# Connectors.net
KiCad netlist of a schematic drawn in Altium Designer
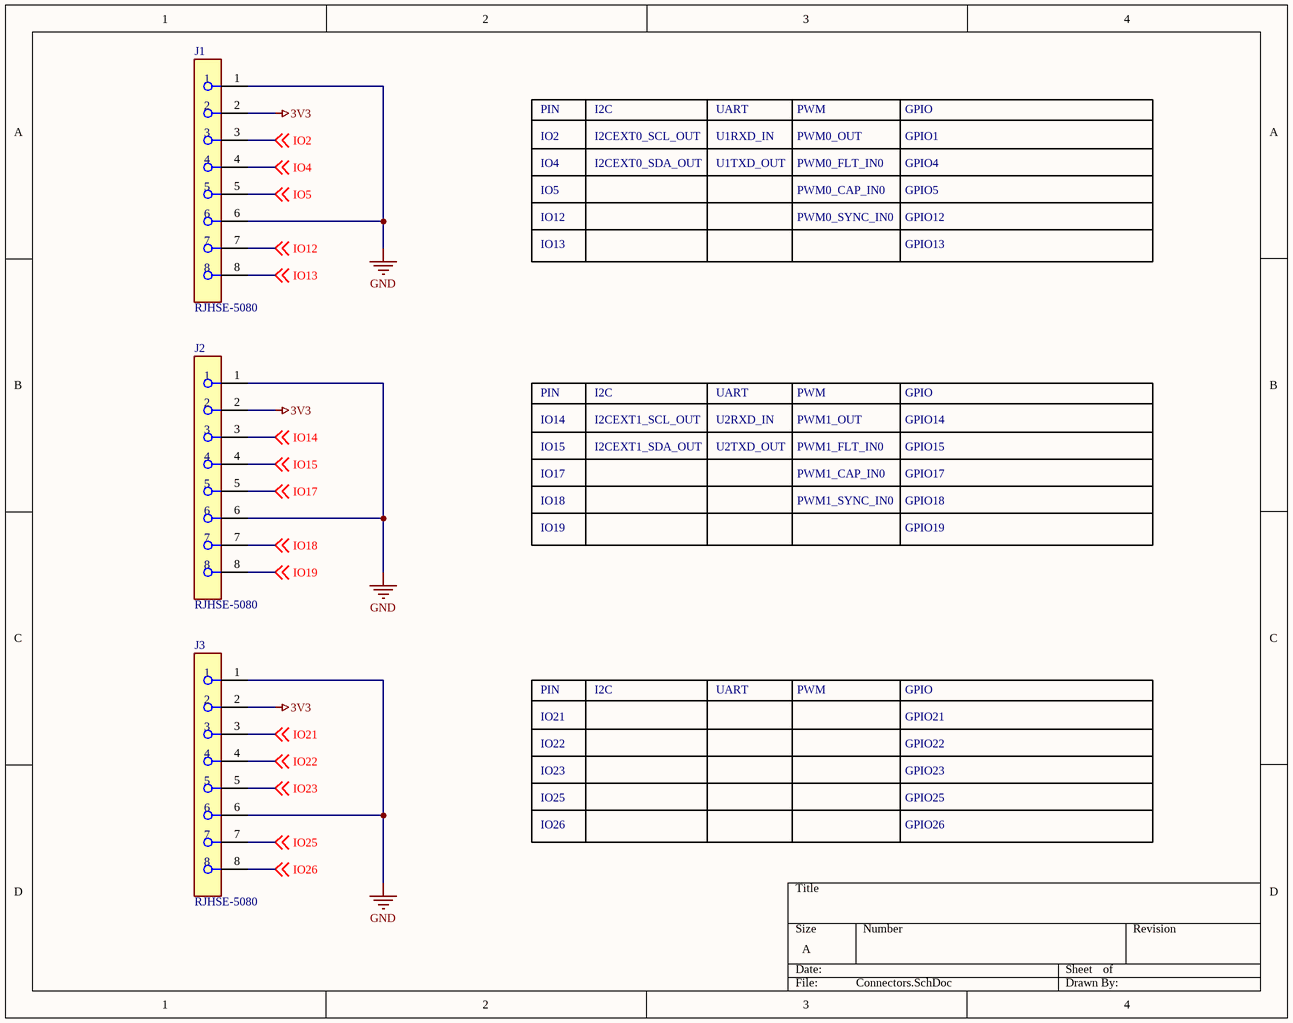
[diagram p0: Connectors.SchDoc]

(export (version "E")
  (design (tool "Eeschema 10.0.6"))
  (components
    (comp (ref "J1")
      (value "RJHSE-5080")
      (footprint "FP-RJHSE-5080-MFG")
      (description "CONN MOD JACK 8P8C R/A UNSHLD")
      (fields
        (field (name "OCTOPART") "https://octopart.com/rjhse-5080-amphenol-45060")
        (field (name "MANUFACTURER") "Amphenol")
      )
      (libsource (lib "Altium Content Vault") (part "b0a0b555dd3abf3683e7c330df25cc4"))
    )
    (comp (ref "J2")
      (value "RJHSE-5080")
      (footprint "FP-RJHSE-5080-MFG")
      (description "CONN MOD JACK 8P8C R/A UNSHLD")
      (fields
        (field (name "OCTOPART") "https://octopart.com/rjhse-5080-amphenol-45060")
        (field (name "MANUFACTURER") "Amphenol")
      )
      (libsource (lib "Altium Content Vault") (part "b0a0b555dd3abf3683e7c330df25cc4"))
    )
    (comp (ref "J3")
      (value "RJHSE-5080")
      (footprint "FP-RJHSE-5080-MFG")
      (description "CONN MOD JACK 8P8C R/A UNSHLD")
      (fields
        (field (name "OCTOPART") "https://octopart.com/rjhse-5080-amphenol-45060")
        (field (name "MANUFACTURER") "Amphenol")
      )
      (libsource (lib "Altium Content Vault") (part "b0a0b555dd3abf3683e7c330df25cc4"))
    )
  )
  (nets
    (net (code "1") (name "3V3") (class "Default")
      (node (ref "J1") (pin "2") (pinfunction "2_2") (pintype "passive"))
      (node (ref "J2") (pin "2") (pinfunction "2_2") (pintype "passive"))
      (node (ref "J3") (pin "2") (pinfunction "2_2") (pintype "passive"))
    )
    (net (code "2") (name "GND") (class "Default")
      (node (ref "J1") (pin "1") (pinfunction "1_1") (pintype "passive"))
      (node (ref "J1") (pin "6") (pinfunction "6_6") (pintype "passive"))
      (node (ref "J2") (pin "1") (pinfunction "1_1") (pintype "passive"))
      (node (ref "J2") (pin "6") (pinfunction "6_6") (pintype "passive"))
      (node (ref "J3") (pin "1") (pinfunction "1_1") (pintype "passive"))
      (node (ref "J3") (pin "6") (pinfunction "6_6") (pintype "passive"))
    )
    (net (code "3") (name "IO2") (class "Default")
      (node (ref "J1") (pin "3") (pinfunction "3_3") (pintype "passive"))
    )
    (net (code "4") (name "IO4") (class "Default")
      (node (ref "J1") (pin "4") (pinfunction "4_4") (pintype "passive"))
    )
    (net (code "5") (name "IO5") (class "Default")
      (node (ref "J1") (pin "5") (pinfunction "5_5") (pintype "passive"))
    )
    (net (code "6") (name "IO12") (class "Default")
      (node (ref "J1") (pin "7") (pinfunction "7_7") (pintype "passive"))
    )
    (net (code "7") (name "IO13") (class "Default")
      (node (ref "J1") (pin "8") (pinfunction "8_8") (pintype "passive"))
    )
    (net (code "8") (name "IO14") (class "Default")
      (node (ref "J2") (pin "3") (pinfunction "3_3") (pintype "passive"))
    )
    (net (code "9") (name "IO15") (class "Default")
      (node (ref "J2") (pin "4") (pinfunction "4_4") (pintype "passive"))
    )
    (net (code "10") (name "IO17") (class "Default")
      (node (ref "J2") (pin "5") (pinfunction "5_5") (pintype "passive"))
    )
    (net (code "11") (name "IO18") (class "Default")
      (node (ref "J2") (pin "7") (pinfunction "7_7") (pintype "passive"))
    )
    (net (code "12") (name "IO19") (class "Default")
      (node (ref "J2") (pin "8") (pinfunction "8_8") (pintype "passive"))
    )
    (net (code "13") (name "IO21") (class "Default")
      (node (ref "J3") (pin "3") (pinfunction "3_3") (pintype "passive"))
    )
    (net (code "14") (name "IO22") (class "Default")
      (node (ref "J3") (pin "4") (pinfunction "4_4") (pintype "passive"))
    )
    (net (code "15") (name "IO23") (class "Default")
      (node (ref "J3") (pin "5") (pinfunction "5_5") (pintype "passive"))
    )
    (net (code "16") (name "IO25") (class "Default")
      (node (ref "J3") (pin "7") (pinfunction "7_7") (pintype "passive"))
    )
    (net (code "17") (name "IO26") (class "Default")
      (node (ref "J3") (pin "8") (pinfunction "8_8") (pintype "passive"))
    )
  )
)
